# SCH_Sensor_Node.net
KiCad netlist of a schematic drawn in Altium Designer
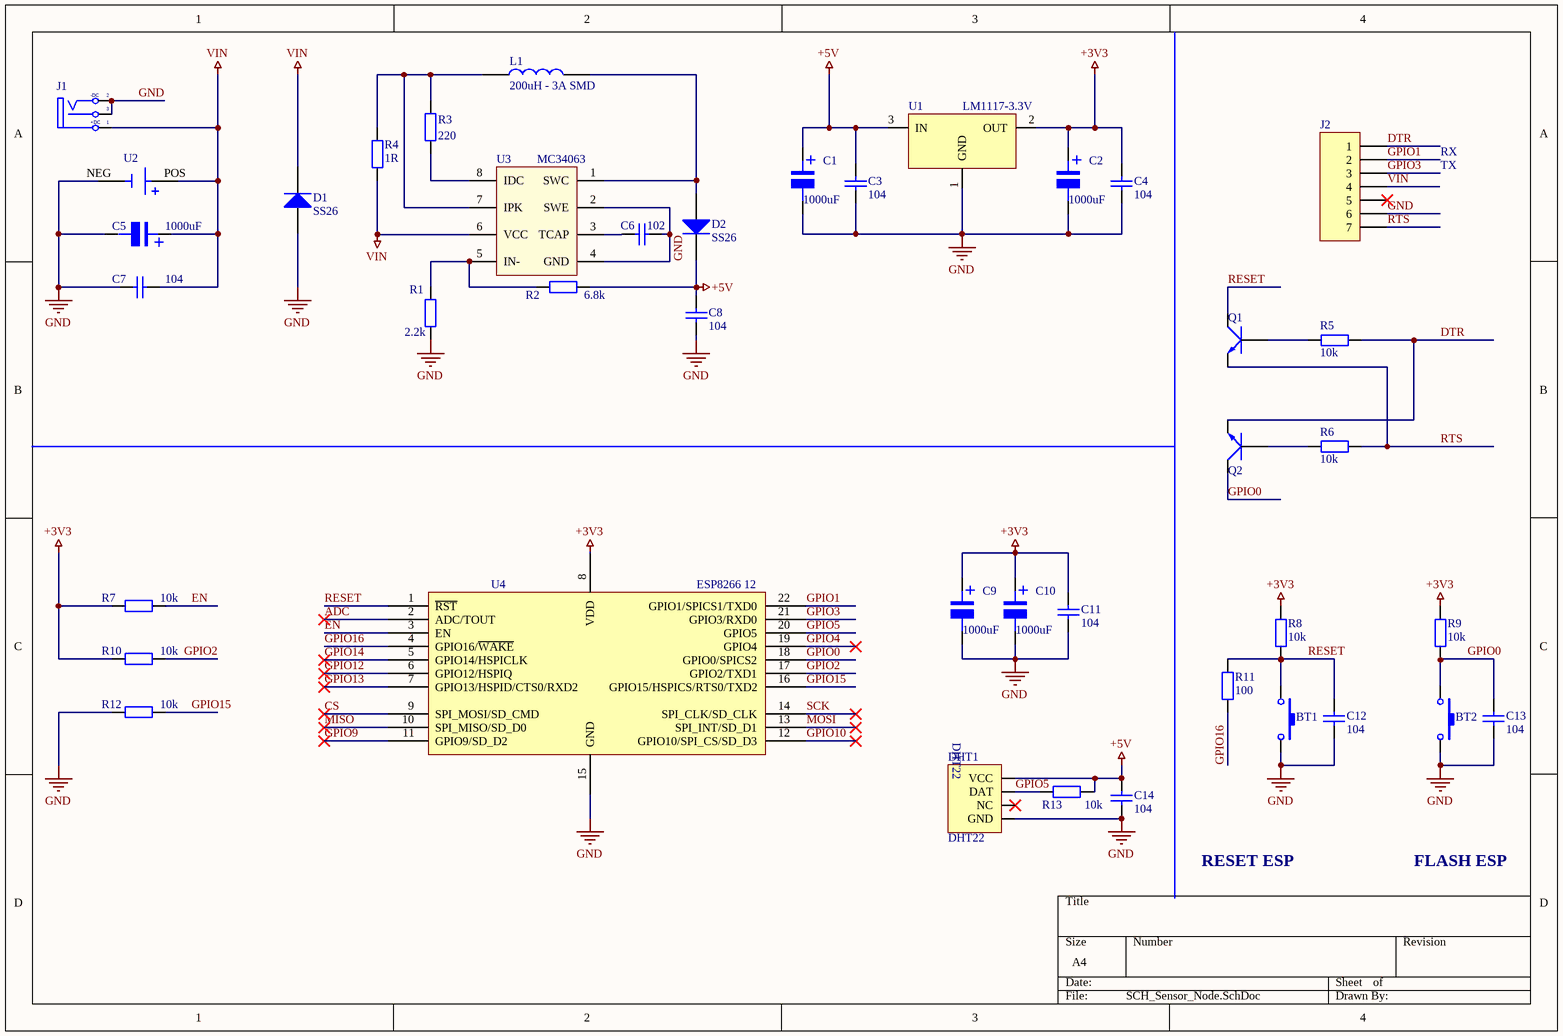
[diagram p0: SCH_Sensor_Node.SchDoc]

(export (version "E")
  (design (tool "Eeschema 10.0.6"))
  (components
    (comp (ref "BT1")
      (value "Nut Nhan 2 Chan SMD 3x6x2.5")
      (footprint "Nut Nhan 2 Chan SMD 3x6x2.5")
      (libsource (lib "Altium_Lib_by_KhueNguyenCreator") (part "Nut Nhan 2 Chan SMD 3x6x2.5"))
    )
    (comp (ref "BT2")
      (value "Nut Nhan 2 Chan SMD 3x6x2.5")
      (footprint "Nut Nhan 2 Chan SMD 3x6x2.5")
      (libsource (lib "Altium_Lib_by_KhueNguyenCreator") (part "Nut Nhan 2 Chan SMD 3x6x2.5"))
    )
    (comp (ref "C1")
      (value "1000uF")
      (footprint "tu nhom 10 (G)")
      (description "Dán")
      (libsource (lib "") (part "Tu Nhom 1000uF 10V_1"))
    )
    (comp (ref "C2")
      (value "1000uF")
      (footprint "tu nhom 10 (G)")
      (description "Dán")
      (libsource (lib "") (part "Tu Nhom 1000uF 10V_1"))
    )
    (comp (ref "C3")
      (value "104")
      (footprint "tu 0805")
      (description "Dán")
      (libsource (lib "Altium_Lib_by_KhueNguyenCreator") (part "Tu 0805 104 50V 10%"))
    )
    (comp (ref "C4")
      (value "104")
      (footprint "tu 0805")
      (description "Dán")
      (libsource (lib "Altium_Lib_by_KhueNguyenCreator") (part "Tu 0805 104 50V 10%"))
    )
    (comp (ref "C5")
      (value "1000uF")
      (footprint "tu nhom 10 (G)")
      (description "Dán")
      (libsource (lib "Altium_Lib_by_KhueNguyenCreator") (part "Tu Nhom 1000uF 10V"))
    )
    (comp (ref "C6")
      (value "102")
      (footprint "tu 0805")
      (description "Dán")
      (libsource (lib "Altium_Lib_by_KhueNguyenCreator") (part "Tu 0805 102 50V 10%"))
    )
    (comp (ref "C7")
      (value "104")
      (footprint "tu 0805")
      (description "Dán")
      (libsource (lib "Altium_Lib_by_KhueNguyenCreator") (part "Tu 0805 104 50V 10%"))
    )
    (comp (ref "C8")
      (value "104")
      (footprint "tu 0805")
      (description "Dán")
      (libsource (lib "Altium_Lib_by_KhueNguyenCreator") (part "Tu 0805 104 50V 10%"))
    )
    (comp (ref "C9")
      (value "1000uF")
      (footprint "tu nhom 10 (G)")
      (description "Dán")
      (libsource (lib "") (part "Tu Nhom 1000uF 10V_1"))
    )
    (comp (ref "C10")
      (value "1000uF")
      (footprint "tu nhom 10 (G)")
      (description "Dán")
      (libsource (lib "") (part "Tu Nhom 1000uF 10V_1"))
    )
    (comp (ref "C11")
      (value "104")
      (footprint "tu 0805")
      (description "Dán")
      (libsource (lib "Altium_Lib_by_KhueNguyenCreator") (part "Tu 0805 104 50V 10%"))
    )
    (comp (ref "C12")
      (value "104")
      (footprint "tu 0805")
      (description "Dán")
      (libsource (lib "Altium_Lib_by_KhueNguyenCreator") (part "Tu 0805 104 50V 10%"))
    )
    (comp (ref "C13")
      (value "104")
      (footprint "tu 0805")
      (description "Dán")
      (libsource (lib "Altium_Lib_by_KhueNguyenCreator") (part "Tu 0805 104 50V 10%"))
    )
    (comp (ref "C14")
      (value "104")
      (footprint "tu 0805")
      (description "Dán")
      (libsource (lib "Altium_Lib_by_KhueNguyenCreator") (part "Tu 0805 104 50V 10%"))
    )
    (comp (ref "D1")
      (value "SS26")
      (footprint "CAPM4336X25N")
      (description "Dán")
      (libsource (lib "SS26") (part "Diode SS26"))
    )
    (comp (ref "D2")
      (value "SS26")
      (footprint "CAPM4336X25N")
      (description "Dán")
      (libsource (lib "SS26") (part "Diode SS26"))
    )
    (comp (ref "DHT1")
      (value "DHT22")
      (footprint "DHT22-SMD")
      (fields
        (field (name "MANUFACTURER") "Würth Elektronik eiSos GmbH")
        (field (name "PARTNO") "613004143121")
        (field (name "CREATED BY") "Karrer Zheng")
      )
      (libsource (lib "TechMT.VN_Lib_Project v2") (part "DHT22"))
    )
    (comp (ref "J1")
      (value "JACK DC 5.5")
      (footprint "JACK DC 5.5")
      (libsource (lib "Altium_Lib_by_KhueNguyenCreator") (part "JACK DC 5.5"))
    )
    (comp (ref "J2")
      (value "Header 7")
      (footprint "HDR1X7")
      (description "Header, 7-Pin")
      (fields (field (name "PUBLISHER") "Altium Limited"))
      (libsource (lib "Miscellaneous Connectors") (part "Header 7"))
    )
    (comp (ref "L1")
      (value "200uH - 3A SMD")
      (footprint "Cuon Cam 12x12x10")
      (description "Dán")
      (libsource (lib "Altium_Lib_by_KhueNguyenCreator") (part "CUON CAM 100uH SMD"))
    )
    (comp (ref "Q1")
      (value "HF")
      (footprint "SOT23")
      (description "NPN transistor")
      (libsource (lib "Altium_Lib_by_KhueNguyenCreator") (part "C1815 HF SMD"))
    )
    (comp (ref "Q2")
      (value "HF")
      (footprint "SOT23")
      (description "NPN transistor")
      (libsource (lib "Altium_Lib_by_KhueNguyenCreator") (part "C1815 HF SMD"))
    )
    (comp (ref "R1")
      (value "2.2k")
      (footprint "tro smd 0805")
      (description "Dán")
      (libsource (lib "Altium_Lib_by_KhueNguyenCreator") (part "Tro 0805 1% 10k"))
    )
    (comp (ref "R2")
      (value "6.8k")
      (footprint "tro smd 0805")
      (description "Dán")
      (libsource (lib "Altium_Lib_by_KhueNguyenCreator") (part "Tro 0805 1% 10k"))
    )
    (comp (ref "R3")
      (value "220")
      (footprint "tro smd 0805")
      (description "Dán")
      (libsource (lib "Altium_Lib_by_KhueNguyenCreator") (part "Tro 0805 1% 10k"))
    )
    (comp (ref "R4")
      (value "1R")
      (footprint "tro smd 0805")
      (description "Dán")
      (libsource (lib "Altium_Lib_by_KhueNguyenCreator") (part "Tro 0805 1% 1R"))
    )
    (comp (ref "R5")
      (value "10k")
      (footprint "tro smd 0805")
      (description "Dán")
      (libsource (lib "Altium_Lib_by_KhueNguyenCreator") (part "Tro 0805 1% 10k"))
    )
    (comp (ref "R6")
      (value "10k")
      (footprint "tro smd 0805")
      (description "Dán")
      (libsource (lib "Altium_Lib_by_KhueNguyenCreator") (part "Tro 0805 1% 10k"))
    )
    (comp (ref "R7")
      (value "10k")
      (footprint "tro smd 0805")
      (description "Dán")
      (libsource (lib "Altium_Lib_by_KhueNguyenCreator") (part "Tro 0805 1% 10k"))
    )
    (comp (ref "R8")
      (value "10k")
      (footprint "tro smd 0805")
      (description "Dán")
      (libsource (lib "Altium_Lib_by_KhueNguyenCreator") (part "Tro 0805 1% 10k"))
    )
    (comp (ref "R9")
      (value "10k")
      (footprint "tro smd 0805")
      (description "Dán")
      (libsource (lib "Altium_Lib_by_KhueNguyenCreator") (part "Tro 0805 1% 10k"))
    )
    (comp (ref "R10")
      (value "10k")
      (footprint "tro smd 0805")
      (description "Dán")
      (libsource (lib "Altium_Lib_by_KhueNguyenCreator") (part "Tro 0805 1% 10k"))
    )
    (comp (ref "R11")
      (value "100")
      (footprint "tro smd 0805")
      (description "Dán")
      (libsource (lib "Altium_Lib_by_KhueNguyenCreator") (part "Tro 0805 5% 100R"))
    )
    (comp (ref "R12")
      (value "10k")
      (footprint "tro smd 0805")
      (description "Dán")
      (libsource (lib "Altium_Lib_by_KhueNguyenCreator") (part "Tro 0805 1% 10k"))
    )
    (comp (ref "R13")
      (value "10k")
      (footprint "tro smd 0805")
      (description "Dán")
      (libsource (lib "Altium_Lib_by_KhueNguyenCreator") (part "Tro 0805 1% 10k"))
    )
    (comp (ref "U1")
      (value "LM1117-3.3V")
      (footprint "SOT223")
      (description "800mA Low-Dropout Linear Regulator")
      (fields (field (name "CREATOR") "Nguyen Ba Bien"))
      (libsource (lib "TechMT.VN_Lib_Project v2") (part "LM1117"))
    )
    (comp (ref "U2")
      (value "BK-18650-PC2")
      (footprint "BAT_BK-18650-PC2")
      (description "Battery Holder _Open_ 18650 1 Cell PC Pin")
      (fields (field (name "MF") "MPD"))
      (libsource (lib "BK-18650-PC2") (part "BK-18650-PC2"))
    )
    (comp (ref "U3")
      (value "MC34063")
      (footprint "SOIC127P600X175-8N")
      (libsource (lib "MC34063") (part "MC34063"))
    )
    (comp (ref "U4")
      (value "ESP8266 12")
      (footprint "ESP8266 12")
      (description "ESP8266 12 22 Pin")
      (libsource (lib "Altium_Lib_by_KhueNguyenCreator") (part "ESP8266 12"))
    )
  )
  (nets
    (net (code "1") (name "+3V3") (class "Default")
      (node (ref "C10") (pin "1") (pinfunction "1_1") (pintype "passive"))
      (node (ref "C11") (pin "1") (pinfunction "1_1") (pintype "passive"))
      (node (ref "C2") (pin "1") (pinfunction "1_1") (pintype "passive"))
      (node (ref "C4") (pin "1") (pinfunction "1_1") (pintype "passive"))
      (node (ref "C9") (pin "1") (pinfunction "1_1") (pintype "passive"))
      (node (ref "R10") (pin "2") (pinfunction "2_2") (pintype "passive"))
      (node (ref "R7") (pin "2") (pinfunction "2_2") (pintype "passive"))
      (node (ref "R8") (pin "2") (pinfunction "2_2") (pintype "passive"))
      (node (ref "R9") (pin "2") (pinfunction "2_2") (pintype "passive"))
      (node (ref "U1") (pin "2") (pinfunction "OUT_2") (pintype "passive"))
      (node (ref "U4") (pin "8") (pinfunction "VDD_8") (pintype "passive"))
    )
    (net (code "2") (name "+5V") (class "Default")
      (node (ref "C1") (pin "1") (pinfunction "1_1") (pintype "passive"))
      (node (ref "C14") (pin "1") (pinfunction "1_1") (pintype "passive"))
      (node (ref "C3") (pin "1") (pinfunction "1_1") (pintype "passive"))
      (node (ref "C8") (pin "1") (pinfunction "1_1") (pintype "passive"))
      (node (ref "D2") (pin "2") (pinfunction "K_2") (pintype "passive"))
      (node (ref "DHT1") (pin "1") (pinfunction "VCC_1") (pintype "passive"))
      (node (ref "R13") (pin "1") (pinfunction "1_1") (pintype "passive"))
      (node (ref "R2") (pin "1") (pinfunction "1_1") (pintype "passive"))
      (node (ref "U1") (pin "3") (pinfunction "IN_3") (pintype "passive"))
    )
    (net (code "3") (name "/ADC") (class "Default")
      (node (ref "U4") (pin "2") (pinfunction "ADC/TOUT_2") (pintype "passive+no_connect"))
    )
    (net (code "4") (name "/CS") (class "Default")
      (node (ref "U4") (pin "9") (pinfunction "SPI_MOSI/SD_CMD_9") (pintype "passive+no_connect"))
    )
    (net (code "5") (name "/DTR") (class "Default")
      (node (ref "J2") (pin "1") (pinfunction "1_1") (pintype "passive"))
      (node (ref "Q2") (pin "2") (pinfunction "E_2") (pintype "passive"))
      (node (ref "R5") (pin "1") (pinfunction "1_1") (pintype "passive"))
    )
    (net (code "6") (name "/EN") (class "Default")
      (node (ref "R7") (pin "1") (pinfunction "1_1") (pintype "passive"))
      (node (ref "U4") (pin "3") (pinfunction "EN_3") (pintype "passive"))
    )
    (net (code "7") (name "/GPIO0") (class "Default")
      (node (ref "BT2") (pin "1") (pinfunction "1_1") (pintype "passive"))
      (node (ref "C13") (pin "1") (pinfunction "1_1") (pintype "passive"))
      (node (ref "Q2") (pin "3") (pinfunction "C_3") (pintype "passive"))
      (node (ref "R9") (pin "1") (pinfunction "1_1") (pintype "passive"))
      (node (ref "U4") (pin "18") (pinfunction "GPIO0/SPICS2_18") (pintype "passive"))
    )
    (net (code "8") (name "/GPIO1") (class "Default")
      (node (ref "J2") (pin "2") (pinfunction "2_2") (pintype "passive"))
      (node (ref "U4") (pin "22") (pinfunction "GPIO1/SPICS1/TXD0_22") (pintype "passive"))
    )
    (net (code "9") (name "/GPIO2") (class "Default")
      (node (ref "R10") (pin "1") (pinfunction "1_1") (pintype "passive"))
      (node (ref "U4") (pin "17") (pinfunction "GPIO2/TXD1_17") (pintype "passive"))
    )
    (net (code "10") (name "/GPIO3") (class "Default")
      (node (ref "J2") (pin "3") (pinfunction "3_3") (pintype "passive"))
      (node (ref "U4") (pin "21") (pinfunction "GPIO3/RXD0_21") (pintype "passive"))
    )
    (net (code "11") (name "/GPIO4") (class "Default")
      (node (ref "U4") (pin "19") (pinfunction "GPIO4_19") (pintype "passive+no_connect"))
    )
    (net (code "12") (name "/GPIO5") (class "Default")
      (node (ref "DHT1") (pin "2") (pinfunction "DAT_2") (pintype "passive"))
      (node (ref "R13") (pin "2") (pinfunction "2_2") (pintype "passive"))
      (node (ref "U4") (pin "20") (pinfunction "GPIO5_20") (pintype "passive"))
    )
    (net (code "13") (name "/GPIO9") (class "Default")
      (node (ref "U4") (pin "11") (pinfunction "GPIO9/SD_D2_11") (pintype "passive+no_connect"))
    )
    (net (code "14") (name "/GPIO10") (class "Default")
      (node (ref "U4") (pin "12") (pinfunction "GPIO10/SPI_CS/SD_D3_12") (pintype "passive+no_connect"))
    )
    (net (code "15") (name "/GPIO12") (class "Default")
      (node (ref "U4") (pin "6") (pinfunction "GPIO12/HSPIQ_6") (pintype "passive+no_connect"))
    )
    (net (code "16") (name "/GPIO13") (class "Default")
      (node (ref "U4") (pin "7") (pinfunction "GPIO13/HSPID/CTS0/RXD2_7") (pintype "passive+no_connect"))
    )
    (net (code "17") (name "/GPIO14") (class "Default")
      (node (ref "U4") (pin "5") (pinfunction "GPIO14/HSPICLK_5") (pintype "passive+no_connect"))
    )
    (net (code "18") (name "/GPIO15") (class "Default")
      (node (ref "R12") (pin "1") (pinfunction "1_1") (pintype "passive"))
      (node (ref "U4") (pin "16") (pinfunction "GPIO15/HSPICS/RTS0/TXD2_16") (pintype "passive"))
    )
    (net (code "19") (name "/GPIO16") (class "Default")
      (node (ref "R11") (pin "1") (pinfunction "1_1") (pintype "passive"))
      (node (ref "U4") (pin "4") (pinfunction "GPIO16/~{WAKE}_4") (pintype "passive"))
    )
    (net (code "20") (name "/MISO") (class "Default")
      (node (ref "U4") (pin "10") (pinfunction "SPI_MISO/SD_D0_10") (pintype "passive+no_connect"))
    )
    (net (code "21") (name "/MOSI") (class "Default")
      (node (ref "U4") (pin "13") (pinfunction "SPI_INT/SD_D1_13") (pintype "passive+no_connect"))
    )
    (net (code "22") (name "/RESET") (class "Default")
      (node (ref "BT1") (pin "1") (pinfunction "1_1") (pintype "passive"))
      (node (ref "C12") (pin "1") (pinfunction "1_1") (pintype "passive"))
      (node (ref "Q1") (pin "3") (pinfunction "C_3") (pintype "passive"))
      (node (ref "R11") (pin "2") (pinfunction "2_2") (pintype "passive"))
      (node (ref "R8") (pin "1") (pinfunction "1_1") (pintype "passive"))
      (node (ref "U4") (pin "1") (pinfunction "~{RST}_1") (pintype "passive"))
    )
    (net (code "23") (name "/RTS") (class "Default")
      (node (ref "J2") (pin "7") (pinfunction "7_7") (pintype "passive"))
      (node (ref "Q1") (pin "2") (pinfunction "E_2") (pintype "passive"))
      (node (ref "R6") (pin "1") (pinfunction "1_1") (pintype "passive"))
    )
    (net (code "24") (name "/SCK") (class "Default")
      (node (ref "U4") (pin "14") (pinfunction "SPI_CLK/SD_CLK_14") (pintype "passive+no_connect"))
    )
    (net (code "25") (name "GND") (class "Default")
      (node (ref "BT1") (pin "2") (pinfunction "2_2") (pintype "passive"))
      (node (ref "BT2") (pin "2") (pinfunction "2_2") (pintype "passive"))
      (node (ref "C1") (pin "2") (pinfunction "2_2") (pintype "passive"))
      (node (ref "C10") (pin "2") (pinfunction "2_2") (pintype "passive"))
      (node (ref "C11") (pin "2") (pinfunction "2_2") (pintype "passive"))
      (node (ref "C12") (pin "2") (pinfunction "2_2") (pintype "passive"))
      (node (ref "C13") (pin "2") (pinfunction "2_2") (pintype "passive"))
      (node (ref "C14") (pin "2") (pinfunction "2_2") (pintype "passive"))
      (node (ref "C2") (pin "2") (pinfunction "2_2") (pintype "passive"))
      (node (ref "C3") (pin "2") (pinfunction "2_2") (pintype "passive"))
      (node (ref "C4") (pin "2") (pinfunction "2_2") (pintype "passive"))
      (node (ref "C5") (pin "2") (pinfunction "2_2") (pintype "passive"))
      (node (ref "C6") (pin "1") (pinfunction "1_1") (pintype "passive"))
      (node (ref "C7") (pin "1") (pinfunction "1_1") (pintype "passive"))
      (node (ref "C8") (pin "2") (pinfunction "2_2") (pintype "passive"))
      (node (ref "C9") (pin "2") (pinfunction "2_2") (pintype "passive"))
      (node (ref "D1") (pin "1") (pinfunction "A_1") (pintype "passive"))
      (node (ref "DHT1") (pin "4") (pinfunction "GND_4") (pintype "passive"))
      (node (ref "J1") (pin "2") (pinfunction "TN_2") (pintype "passive"))
      (node (ref "J1") (pin "3") (pinfunction "S_3") (pintype "power_in"))
      (node (ref "J2") (pin "6") (pinfunction "6_6") (pintype "passive"))
      (node (ref "R1") (pin "2") (pinfunction "2_2") (pintype "passive"))
      (node (ref "R12") (pin "2") (pinfunction "2_2") (pintype "passive"))
      (node (ref "U1") (pin "1") (pinfunction "GND_1") (pintype "passive"))
      (node (ref "U2") (pin "NEG") (pinfunction "NEG_NEG") (pintype "passive"))
      (node (ref "U3") (pin "2") (pinfunction "SWE_2") (pintype "passive"))
      (node (ref "U3") (pin "4") (pinfunction "GND_4") (pintype "passive"))
      (node (ref "U4") (pin "15") (pinfunction "GND_15") (pintype "passive"))
    )
    (net (code "26") (name "Net-(D2-A)") (class "Default")
      (node (ref "D2") (pin "1") (pinfunction "A_1") (pintype "passive"))
      (node (ref "L1") (pin "2") (pinfunction "2_2") (pintype "passive"))
      (node (ref "U3") (pin "1") (pinfunction "SWC_1") (pintype "passive"))
    )
    (net (code "27") (name "Net-(Q1-B)") (class "Default")
      (node (ref "Q1") (pin "1") (pinfunction "B_1") (pintype "passive"))
      (node (ref "R5") (pin "2") (pinfunction "2_2") (pintype "passive"))
    )
    (net (code "28") (name "Net-(Q2-B)") (class "Default")
      (node (ref "Q2") (pin "1") (pinfunction "B_1") (pintype "passive"))
      (node (ref "R6") (pin "2") (pinfunction "2_2") (pintype "passive"))
    )
    (net (code "29") (name "Net-(U3-IDC)") (class "Default")
      (node (ref "R3") (pin "2") (pinfunction "2_2") (pintype "passive"))
      (node (ref "U3") (pin "8") (pinfunction "IDC_8") (pintype "passive"))
    )
    (net (code "30") (name "Net-(U3-IN-)") (class "Default")
      (node (ref "R1") (pin "1") (pinfunction "1_1") (pintype "passive"))
      (node (ref "R2") (pin "2") (pinfunction "2_2") (pintype "passive"))
      (node (ref "U3") (pin "5") (pinfunction "IN-_5") (pintype "passive"))
    )
    (net (code "31") (name "Net-(U3-IPK)") (class "Default")
      (node (ref "L1") (pin "1") (pinfunction "1_1") (pintype "passive"))
      (node (ref "R3") (pin "1") (pinfunction "1_1") (pintype "passive"))
      (node (ref "R4") (pin "2") (pinfunction "2_2") (pintype "passive"))
      (node (ref "U3") (pin "7") (pinfunction "IPK_7") (pintype "passive"))
    )
    (net (code "32") (name "Net-(U3-TCAP)") (class "Default")
      (node (ref "C6") (pin "2") (pinfunction "2_2") (pintype "passive"))
      (node (ref "U3") (pin "3") (pinfunction "TCAP_3") (pintype "passive"))
    )
    (net (code "33") (name "VIN") (class "Default")
      (node (ref "C5") (pin "1") (pinfunction "1_1") (pintype "passive"))
      (node (ref "C7") (pin "2") (pinfunction "2_2") (pintype "passive"))
      (node (ref "D1") (pin "2") (pinfunction "K_2") (pintype "passive"))
      (node (ref "J1") (pin "1") (pinfunction "T_1") (pintype "passive"))
      (node (ref "J2") (pin "4") (pinfunction "4_4") (pintype "passive"))
      (node (ref "R4") (pin "1") (pinfunction "1_1") (pintype "passive"))
      (node (ref "U2") (pin "POS") (pinfunction "POS_POS") (pintype "passive"))
      (node (ref "U3") (pin "6") (pinfunction "VCC_6") (pintype "passive"))
    )
    (net (code "34") (name "unconnected-(DHT1-NC-Pad3)") (class "Default")
      (node (ref "DHT1") (pin "3") (pinfunction "NC_3") (pintype "passive+no_connect"))
    )
    (net (code "35") (name "unconnected-(J2-Pad5)") (class "Default")
      (node (ref "J2") (pin "5") (pinfunction "5_5") (pintype "passive+no_connect"))
    )
  )
)
